# xclock_A.net
KiCad netlist of a schematic drawn in EAGLE
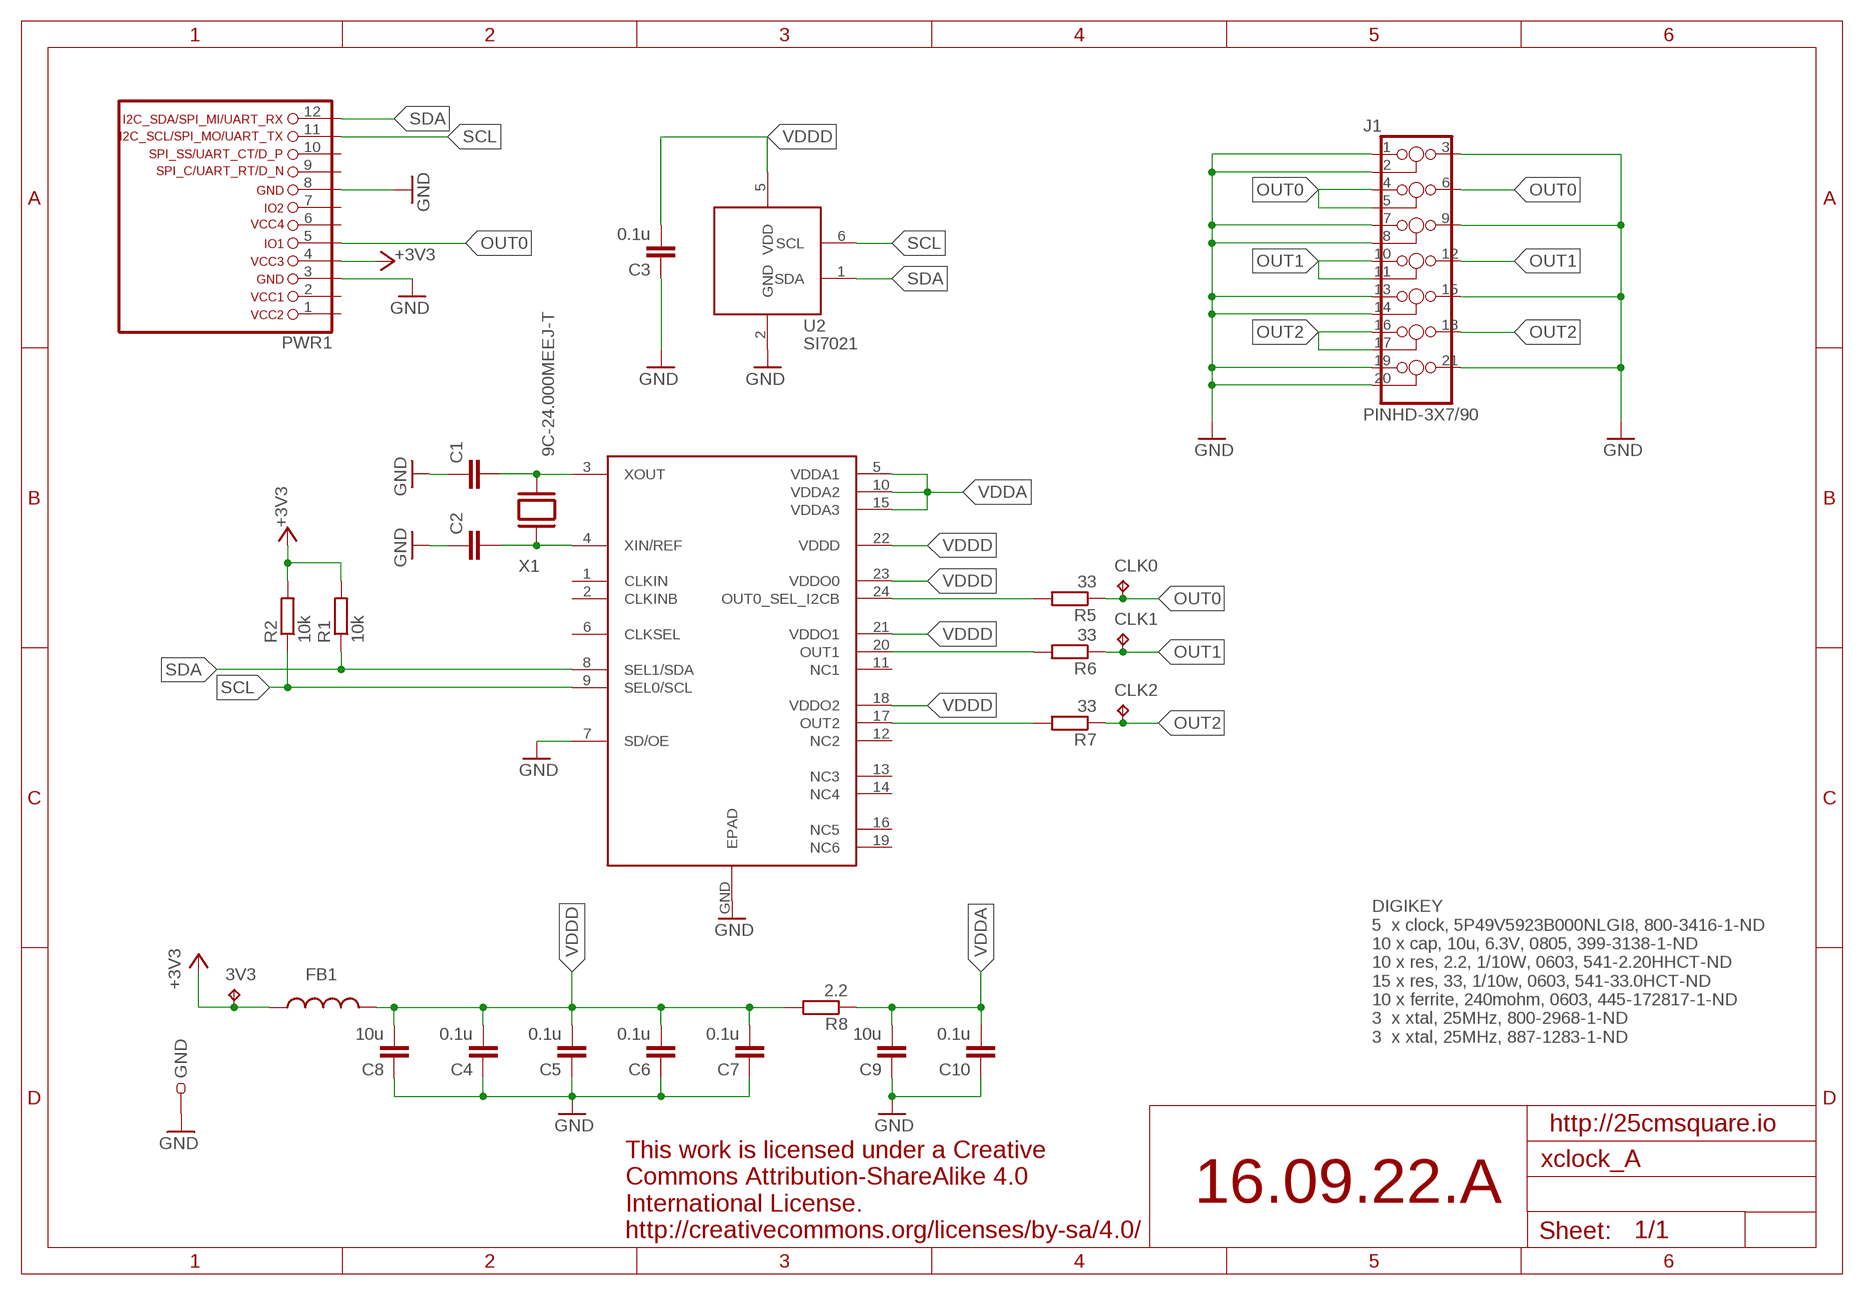
[diagram p0: schematic, sheet 1]

(export (version "E")
  (design (tool "Eeschema 10.0.6"))
  (components
    (comp (ref "3V3")
      (value "TPB1,27")
      (footprint "eagle-import:B1,27")
      (libsource (lib "eagle-import") (part "TPB1,27"))
    )
    (comp (ref "C1")
      (value "C-EUC0603")
      (footprint "eagle-import:C0603")
      (libsource (lib "eagle-import") (part "C-EUC0603"))
    )
    (comp (ref "C2")
      (value "C-EUC0603")
      (footprint "eagle-import:C0603")
      (libsource (lib "eagle-import") (part "C-EUC0603"))
    )
    (comp (ref "C3")
      (value "0.1u")
      (footprint "eagle-import:C0603")
      (libsource (lib "eagle-import") (part "C-EUC0603"))
    )
    (comp (ref "C4")
      (value "0.1u")
      (footprint "eagle-import:C0603")
      (libsource (lib "eagle-import") (part "C-EUC0603"))
    )
    (comp (ref "C5")
      (value "0.1u")
      (footprint "eagle-import:C0603")
      (libsource (lib "eagle-import") (part "C-EUC0603"))
    )
    (comp (ref "C6")
      (value "0.1u")
      (footprint "eagle-import:C0603")
      (libsource (lib "eagle-import") (part "C-EUC0603"))
    )
    (comp (ref "C7")
      (value "0.1u")
      (footprint "eagle-import:C0603")
      (libsource (lib "eagle-import") (part "C-EUC0603"))
    )
    (comp (ref "C8")
      (value "10u")
      (footprint "eagle-import:C0805")
      (libsource (lib "eagle-import") (part "C-EUC0805"))
    )
    (comp (ref "C9")
      (value "10u")
      (footprint "eagle-import:C0805")
      (libsource (lib "eagle-import") (part "C-EUC0805"))
    )
    (comp (ref "C10")
      (value "0.1u")
      (footprint "eagle-import:C0603")
      (libsource (lib "eagle-import") (part "C-EUC0603"))
    )
    (comp (ref "CLK0")
      (value "TPB1,27")
      (footprint "eagle-import:B1,27")
      (libsource (lib "eagle-import") (part "TPB1,27"))
    )
    (comp (ref "CLK1")
      (value "TPB1,27")
      (footprint "eagle-import:B1,27")
      (libsource (lib "eagle-import") (part "TPB1,27"))
    )
    (comp (ref "CLK2")
      (value "TPB1,27")
      (footprint "eagle-import:B1,27")
      (libsource (lib "eagle-import") (part "TPB1,27"))
    )
    (comp (ref "FB1")
      (value "L0603(1608)")
      (footprint "eagle-import:L0603")
      (libsource (lib "eagle-import") (part "L0603(1608)"))
    )
    (comp (ref "GND")
      (value "TEST-22-MULTICOMP")
      (footprint "eagle-import:TEST_1MM")
      (libsource (lib "eagle-import") (part "TEST-22-MULTICOMP"))
    )
    (comp (ref "J1")
      (value "PINHD-3X7/90")
      (footprint "eagle-import:3X07_90")
      (libsource (lib "eagle-import") (part "PINHD-3X7/90"))
    )
    (comp (ref "PWR1")
      (value "LIWE_12_PIN_PWR")
      (footprint "eagle-import:LIWE_12_PIN")
      (libsource (lib "eagle-import") (part "LIWE_12_PIN_PWR"))
    )
    (comp (ref "R1")
      (value "10k")
      (footprint "eagle-import:R0603")
      (libsource (lib "eagle-import") (part "R-EU_R0603"))
    )
    (comp (ref "R2")
      (value "10k")
      (footprint "eagle-import:R0603")
      (libsource (lib "eagle-import") (part "R-EU_R0603"))
    )
    (comp (ref "R5")
      (value "33")
      (footprint "eagle-import:R0603")
      (libsource (lib "eagle-import") (part "R-EU_R0603"))
    )
    (comp (ref "R6")
      (value "33")
      (footprint "eagle-import:R0603")
      (libsource (lib "eagle-import") (part "R-EU_R0603"))
    )
    (comp (ref "R7")
      (value "33")
      (footprint "eagle-import:R0603")
      (libsource (lib "eagle-import") (part "R-EU_R0603"))
    )
    (comp (ref "R8")
      (value "2.2")
      (footprint "eagle-import:R0603")
      (libsource (lib "eagle-import") (part "R-EU_R0603"))
    )
    (comp (ref "U1")
      (value "5P49V5923")
      (footprint "eagle-import:VFQFPN_24_4X4")
      (libsource (lib "eagle-import") (part "5P49V5923"))
    )
    (comp (ref "U2")
      (value "SI7021")
      (footprint "eagle-import:SI7021")
      (libsource (lib "eagle-import") (part "SI7021"))
    )
    (comp (ref "X1")
      (value "9C-24.000MEEJ-T")
      (footprint "eagle-import:TXC_SMD_HC-49S")
      (libsource (lib "eagle-import") (part "TXC_9C"))
    )
  )
  (nets
    (net (code "1") (name "+3V3") (class "Default")
      (node (ref "3V3") (pin "TP") (pinfunction "TP_TP") (pintype "input"))
      (node (ref "FB1") (pin "1") (pinfunction "1_1") (pintype "passive"))
      (node (ref "PWR1") (pin "4") (pinfunction "4_4") (pintype "passive"))
      (node (ref "R1") (pin "2") (pinfunction "2_2") (pintype "passive"))
      (node (ref "R2") (pin "2") (pinfunction "2_2") (pintype "passive"))
    )
    (net (code "2") (name "GND") (class "Default")
      (node (ref "C1") (pin "1") (pinfunction "1_1") (pintype "passive"))
      (node (ref "C10") (pin "1") (pinfunction "1_1") (pintype "passive"))
      (node (ref "C2") (pin "1") (pinfunction "1_1") (pintype "passive"))
      (node (ref "C3") (pin "1") (pinfunction "1_1") (pintype "passive"))
      (node (ref "C4") (pin "1") (pinfunction "1_1") (pintype "passive"))
      (node (ref "C5") (pin "1") (pinfunction "1_1") (pintype "passive"))
      (node (ref "C6") (pin "1") (pinfunction "1_1") (pintype "passive"))
      (node (ref "C7") (pin "1") (pinfunction "1_1") (pintype "passive"))
      (node (ref "C8") (pin "1") (pinfunction "1_1") (pintype "passive"))
      (node (ref "C9") (pin "1") (pinfunction "1_1") (pintype "passive"))
      (node (ref "GND") (pin "1") (pinfunction "1_1") (pintype "passive"))
      (node (ref "J1") (pin "1") (pinfunction "1_1") (pintype "passive"))
      (node (ref "J1") (pin "13") (pinfunction "13_13") (pintype "passive"))
      (node (ref "J1") (pin "14") (pinfunction "14_14") (pintype "passive"))
      (node (ref "J1") (pin "15") (pinfunction "15_15") (pintype "passive"))
      (node (ref "J1") (pin "19") (pinfunction "19_19") (pintype "passive"))
      (node (ref "J1") (pin "2") (pinfunction "2_2") (pintype "passive"))
      (node (ref "J1") (pin "20") (pinfunction "20_20") (pintype "passive"))
      (node (ref "J1") (pin "21") (pinfunction "21_21") (pintype "passive"))
      (node (ref "J1") (pin "3") (pinfunction "3_3") (pintype "passive"))
      (node (ref "J1") (pin "7") (pinfunction "7_7") (pintype "passive"))
      (node (ref "J1") (pin "8") (pinfunction "8_8") (pintype "passive"))
      (node (ref "J1") (pin "9") (pinfunction "9_9") (pintype "passive"))
      (node (ref "PWR1") (pin "3") (pinfunction "3_3") (pintype "passive"))
      (node (ref "PWR1") (pin "8") (pinfunction "8_8") (pintype "passive"))
      (node (ref "U1") (pin "7") (pinfunction "SD/OE_7") (pintype "bidirectional"))
      (node (ref "U1") (pin "GND") (pinfunction "EPAD_GND") (pintype "bidirectional"))
      (node (ref "U2") (pin "2") (pinfunction "GND_2") (pintype "power_in"))
    )
    (net (code "3") (name "Net-(U1-OUT0_SEL_I2CB)") (class "Default")
      (node (ref "R5") (pin "2") (pinfunction "2_2") (pintype "passive"))
      (node (ref "U1") (pin "24") (pinfunction "OUT0_SEL_I2CB_24") (pintype "bidirectional"))
    )
    (net (code "4") (name "Net-(U1-OUT1)") (class "Default")
      (node (ref "R6") (pin "2") (pinfunction "2_2") (pintype "passive"))
      (node (ref "U1") (pin "20") (pinfunction "OUT1_20") (pintype "bidirectional"))
    )
    (net (code "5") (name "Net-(U1-OUT2)") (class "Default")
      (node (ref "R7") (pin "2") (pinfunction "2_2") (pintype "passive"))
      (node (ref "U1") (pin "17") (pinfunction "OUT2_17") (pintype "bidirectional"))
    )
    (net (code "6") (name "Net-(U1-XIN{slash}REF)") (class "Default")
      (node (ref "C2") (pin "2") (pinfunction "2_2") (pintype "passive"))
      (node (ref "U1") (pin "4") (pinfunction "XIN/REF_4") (pintype "bidirectional"))
      (node (ref "X1") (pin "1") (pinfunction "1_1") (pintype "passive"))
    )
    (net (code "7") (name "Net-(U1-XOUT)") (class "Default")
      (node (ref "C1") (pin "2") (pinfunction "2_2") (pintype "passive"))
      (node (ref "U1") (pin "3") (pinfunction "XOUT_3") (pintype "bidirectional"))
      (node (ref "X1") (pin "2") (pinfunction "2_2") (pintype "passive"))
    )
    (net (code "8") (name "OUT0") (class "Default")
      (node (ref "CLK0") (pin "TP") (pinfunction "TP_TP") (pintype "input"))
      (node (ref "J1") (pin "4") (pinfunction "4_4") (pintype "passive"))
      (node (ref "J1") (pin "5") (pinfunction "5_5") (pintype "passive"))
      (node (ref "J1") (pin "6") (pinfunction "6_6") (pintype "passive"))
      (node (ref "PWR1") (pin "5") (pinfunction "5_5") (pintype "passive"))
      (node (ref "R5") (pin "1") (pinfunction "1_1") (pintype "passive"))
    )
    (net (code "9") (name "OUT1") (class "Default")
      (node (ref "CLK1") (pin "TP") (pinfunction "TP_TP") (pintype "input"))
      (node (ref "J1") (pin "10") (pinfunction "10_10") (pintype "passive"))
      (node (ref "J1") (pin "11") (pinfunction "11_11") (pintype "passive"))
      (node (ref "J1") (pin "12") (pinfunction "12_12") (pintype "passive"))
      (node (ref "R6") (pin "1") (pinfunction "1_1") (pintype "passive"))
    )
    (net (code "10") (name "OUT2") (class "Default")
      (node (ref "CLK2") (pin "TP") (pinfunction "TP_TP") (pintype "input"))
      (node (ref "J1") (pin "16") (pinfunction "16_16") (pintype "passive"))
      (node (ref "J1") (pin "17") (pinfunction "17_17") (pintype "passive"))
      (node (ref "J1") (pin "18") (pinfunction "18_18") (pintype "passive"))
      (node (ref "R7") (pin "1") (pinfunction "1_1") (pintype "passive"))
    )
    (net (code "11") (name "SCL") (class "Default")
      (node (ref "PWR1") (pin "11") (pinfunction "11_11") (pintype "passive"))
      (node (ref "R2") (pin "1") (pinfunction "1_1") (pintype "passive"))
      (node (ref "U1") (pin "9") (pinfunction "SEL0/SCL_9") (pintype "bidirectional"))
      (node (ref "U2") (pin "6") (pinfunction "SCL_6") (pintype "bidirectional"))
    )
    (net (code "12") (name "SDA") (class "Default")
      (node (ref "PWR1") (pin "12") (pinfunction "12_12") (pintype "passive"))
      (node (ref "R1") (pin "1") (pinfunction "1_1") (pintype "passive"))
      (node (ref "U1") (pin "8") (pinfunction "SEL1/SDA_8") (pintype "bidirectional"))
      (node (ref "U2") (pin "1") (pinfunction "SDA_1") (pintype "bidirectional"))
    )
    (net (code "13") (name "VDDA") (class "Default")
      (node (ref "C10") (pin "2") (pinfunction "2_2") (pintype "passive"))
      (node (ref "C9") (pin "2") (pinfunction "2_2") (pintype "passive"))
      (node (ref "R8") (pin "1") (pinfunction "1_1") (pintype "passive"))
      (node (ref "U1") (pin "10") (pinfunction "VDDA2_10") (pintype "bidirectional"))
      (node (ref "U1") (pin "15") (pinfunction "VDDA3_15") (pintype "bidirectional"))
      (node (ref "U1") (pin "5") (pinfunction "VDDA1_5") (pintype "bidirectional"))
    )
    (net (code "14") (name "VDDD") (class "Default")
      (node (ref "C3") (pin "2") (pinfunction "2_2") (pintype "passive"))
      (node (ref "C4") (pin "2") (pinfunction "2_2") (pintype "passive"))
      (node (ref "C5") (pin "2") (pinfunction "2_2") (pintype "passive"))
      (node (ref "C6") (pin "2") (pinfunction "2_2") (pintype "passive"))
      (node (ref "C7") (pin "2") (pinfunction "2_2") (pintype "passive"))
      (node (ref "C8") (pin "2") (pinfunction "2_2") (pintype "passive"))
      (node (ref "FB1") (pin "2") (pinfunction "2_2") (pintype "passive"))
      (node (ref "R8") (pin "2") (pinfunction "2_2") (pintype "passive"))
      (node (ref "U1") (pin "18") (pinfunction "VDDO2_18") (pintype "bidirectional"))
      (node (ref "U1") (pin "21") (pinfunction "VDDO1_21") (pintype "bidirectional"))
      (node (ref "U1") (pin "22") (pinfunction "VDDD_22") (pintype "bidirectional"))
      (node (ref "U1") (pin "23") (pinfunction "VDDO0_23") (pintype "bidirectional"))
      (node (ref "U2") (pin "5") (pinfunction "VDD_5") (pintype "power_in"))
    )
    (net (code "15") (name "unconnected-(PWR1-Pad1)") (class "Default")
      (node (ref "PWR1") (pin "1") (pinfunction "1_1") (pintype "passive"))
    )
    (net (code "16") (name "unconnected-(PWR1-Pad2)") (class "Default")
      (node (ref "PWR1") (pin "2") (pinfunction "2_2") (pintype "passive"))
    )
    (net (code "17") (name "unconnected-(PWR1-Pad6)") (class "Default")
      (node (ref "PWR1") (pin "6") (pinfunction "6_6") (pintype "passive"))
    )
    (net (code "18") (name "unconnected-(PWR1-Pad7)") (class "Default")
      (node (ref "PWR1") (pin "7") (pinfunction "7_7") (pintype "passive"))
    )
    (net (code "19") (name "unconnected-(PWR1-Pad9)") (class "Default")
      (node (ref "PWR1") (pin "9") (pinfunction "9_9") (pintype "passive"))
    )
    (net (code "20") (name "unconnected-(PWR1-Pad10)") (class "Default")
      (node (ref "PWR1") (pin "10") (pinfunction "10_10") (pintype "passive"))
    )
    (net (code "21") (name "unconnected-(U1-CLKIN-Pad1)") (class "Default")
      (node (ref "U1") (pin "1") (pinfunction "CLKIN_1") (pintype "bidirectional"))
    )
    (net (code "22") (name "unconnected-(U1-CLKINB-Pad2)") (class "Default")
      (node (ref "U1") (pin "2") (pinfunction "CLKINB_2") (pintype "bidirectional"))
    )
    (net (code "23") (name "unconnected-(U1-CLKSEL-Pad6)") (class "Default")
      (node (ref "U1") (pin "6") (pinfunction "CLKSEL_6") (pintype "bidirectional"))
    )
    (net (code "24") (name "unconnected-(U1-NC1-Pad11)") (class "Default")
      (node (ref "U1") (pin "11") (pinfunction "NC1_11") (pintype "bidirectional"))
    )
    (net (code "25") (name "unconnected-(U1-NC2-Pad12)") (class "Default")
      (node (ref "U1") (pin "12") (pinfunction "NC2_12") (pintype "bidirectional"))
    )
    (net (code "26") (name "unconnected-(U1-NC3-Pad13)") (class "Default")
      (node (ref "U1") (pin "13") (pinfunction "NC3_13") (pintype "bidirectional"))
    )
    (net (code "27") (name "unconnected-(U1-NC4-Pad14)") (class "Default")
      (node (ref "U1") (pin "14") (pinfunction "NC4_14") (pintype "bidirectional"))
    )
    (net (code "28") (name "unconnected-(U1-NC5-Pad16)") (class "Default")
      (node (ref "U1") (pin "16") (pinfunction "NC5_16") (pintype "bidirectional"))
    )
    (net (code "29") (name "unconnected-(U1-NC6-Pad19)") (class "Default")
      (node (ref "U1") (pin "19") (pinfunction "NC6_19") (pintype "bidirectional"))
    )
  )
)
